# Radar_Digital.net
KiCad netlist of a schematic drawn in Altium Designer
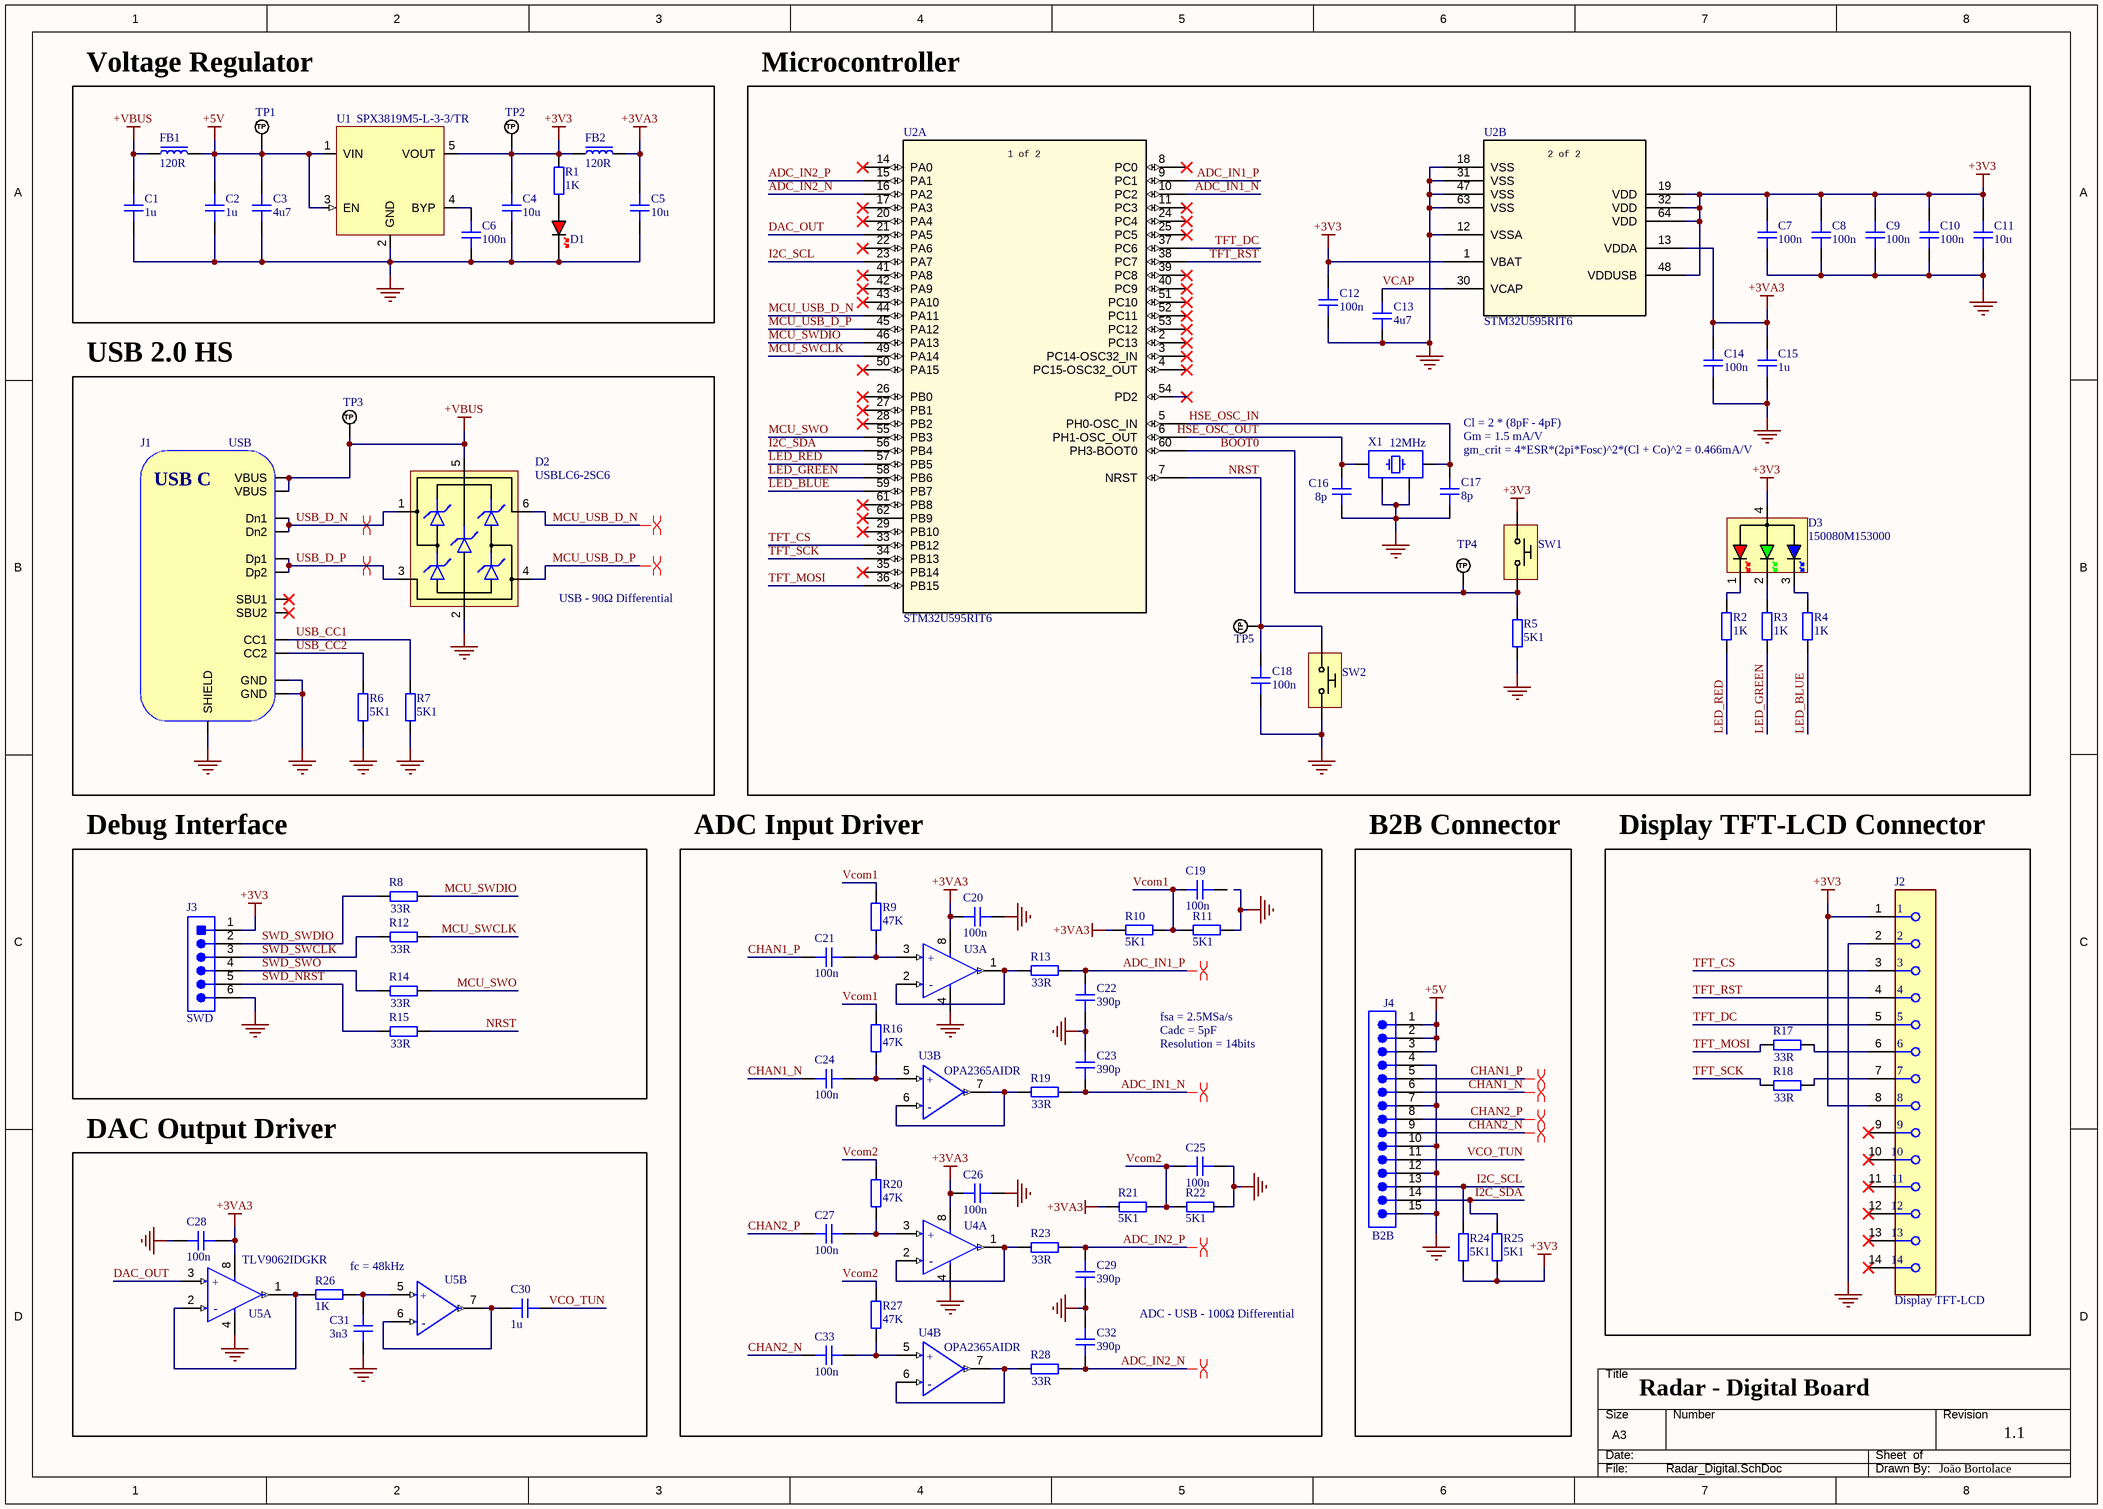
[diagram p0: Radar_Digital.SchDoc]

(export (version "E")
  (design (tool "Eeschema 10.0.6"))
  (components
    (comp (ref "C1")
      (value "1u")
      (footprint "CAP_0603")
      (description "1uF ±10% 25V Ceramic Capacitor X7R 0603")
      (fields
        (field (name "MANUFACTURER") "Samsung Electro-Mechanics")
        (field (name "MANUFACTURER PART NUMBER") "CL10B105KA8NNNC")
      )
      (libsource (lib "Schematic-Lib-PhilsLab") (part "CAP_0603"))
    )
    (comp (ref "C2")
      (value "1u")
      (footprint "CAP_0603")
      (description "1uF ±10% 25V Ceramic Capacitor X7R 0603")
      (fields
        (field (name "MANUFACTURER") "Samsung Electro-Mechanics")
        (field (name "MANUFACTURER PART NUMBER") "CL10B105KA8NNNC")
      )
      (libsource (lib "Schematic-Lib-PhilsLab") (part "CAP_0603"))
    )
    (comp (ref "C3")
      (value "4u7")
      (footprint "CAP_0603")
      (description "4.7uF ±10% 25V Ceramic Capacitor X5R 0603")
      (fields
        (field (name "MANUFACTURER") "Samsung Electro-Mechanics")
        (field (name "MANUFACTURER PART NUMBER") "CL10A475KA8NQNC")
      )
      (libsource (lib "Schematic-Lib-PhilsLab") (part "CAP_0603"))
    )
    (comp (ref "C4")
      (value "10u")
      (footprint "CAP_0805")
      (description "10uF ±10% 16V Ceramic Capacitor X7R 0805")
      (fields
        (field (name "MANUFACTURER") "Samsung Electro-Mechanics")
        (field (name "MANUFACTURER PART NUMBER") "CL21B106KOQNNNE")
      )
      (libsource (lib "Schematic-Lib-PhilsLab") (part "CAP_0805"))
    )
    (comp (ref "C5")
      (value "10u")
      (footprint "CAP_0805")
      (description "10uF ±10% 16V Ceramic Capacitor X7R 0805")
      (fields
        (field (name "MANUFACTURER") "Samsung Electro-Mechanics")
        (field (name "MANUFACTURER PART NUMBER") "CL21B106KOQNNNE")
      )
      (libsource (lib "Schematic-Lib-PhilsLab") (part "CAP_0805"))
    )
    (comp (ref "C6")
      (value "100n")
      (footprint "CAP_0603")
      (description "100nF ±10% 50V Ceramic Capacitor X7R 0603")
      (fields
        (field (name "MANUFACTURER") "Samsung Electro-Mechanics")
        (field (name "MANUFACTURER PART NUMBER") "CL10B104KB8NNNC")
      )
      (libsource (lib "Schematic-Lib-PhilsLab") (part "CAP_0603"))
    )
    (comp (ref "C7")
      (value "100n")
      (footprint "CAP_0603")
      (description "100nF ±10% 50V Ceramic Capacitor X7R 0603")
      (fields
        (field (name "MANUFACTURER") "Samsung Electro-Mechanics")
        (field (name "MANUFACTURER PART NUMBER") "CL10B104KB8NNNC")
      )
      (libsource (lib "Schematic-Lib-PhilsLab") (part "CAP_0603"))
    )
    (comp (ref "C8")
      (value "100n")
      (footprint "CAP_0603")
      (description "100nF ±10% 50V Ceramic Capacitor X7R 0603")
      (fields
        (field (name "MANUFACTURER") "Samsung Electro-Mechanics")
        (field (name "MANUFACTURER PART NUMBER") "CL10B104KB8NNNC")
      )
      (libsource (lib "Schematic-Lib-PhilsLab") (part "CAP_0603"))
    )
    (comp (ref "C9")
      (value "100n")
      (footprint "CAP_0603")
      (description "100nF ±10% 50V Ceramic Capacitor X7R 0603")
      (fields
        (field (name "MANUFACTURER") "Samsung Electro-Mechanics")
        (field (name "MANUFACTURER PART NUMBER") "CL10B104KB8NNNC")
      )
      (libsource (lib "Schematic-Lib-PhilsLab") (part "CAP_0603"))
    )
    (comp (ref "C10")
      (value "100n")
      (footprint "CAP_0603")
      (description "100nF ±10% 50V Ceramic Capacitor X7R 0603")
      (fields
        (field (name "MANUFACTURER") "Samsung Electro-Mechanics")
        (field (name "MANUFACTURER PART NUMBER") "CL10B104KB8NNNC")
      )
      (libsource (lib "Schematic-Lib-PhilsLab") (part "CAP_0603"))
    )
    (comp (ref "C11")
      (value "10u")
      (footprint "CAP_0805")
      (description "10uF ±10% 16V Ceramic Capacitor X7R 0805")
      (fields
        (field (name "MANUFACTURER") "Samsung Electro-Mechanics")
        (field (name "MANUFACTURER PART NUMBER") "CL21B106KOQNNNE")
      )
      (libsource (lib "Schematic-Lib-PhilsLab") (part "CAP_0805"))
    )
    (comp (ref "C12")
      (value "100n")
      (footprint "CAP_0603")
      (description "100nF ±10% 50V Ceramic Capacitor X7R 0603")
      (fields
        (field (name "MANUFACTURER") "Samsung Electro-Mechanics")
        (field (name "MANUFACTURER PART NUMBER") "CL10B104KB8NNNC")
      )
      (libsource (lib "Schematic-Lib-PhilsLab") (part "CAP_0603"))
    )
    (comp (ref "C13")
      (value "4u7")
      (footprint "CAP_0603")
      (description "4.7uF ±10% 25V Ceramic Capacitor X5R 0603")
      (fields
        (field (name "MANUFACTURER") "Samsung Electro-Mechanics")
        (field (name "MANUFACTURER PART NUMBER") "CL10A475KA8NQNC")
      )
      (libsource (lib "Schematic-Lib-PhilsLab") (part "CAP_0603"))
    )
    (comp (ref "C14")
      (value "100n")
      (footprint "CAP_0603")
      (description "100nF ±10% 50V Ceramic Capacitor X7R 0603")
      (fields
        (field (name "MANUFACTURER") "Samsung Electro-Mechanics")
        (field (name "MANUFACTURER PART NUMBER") "CL10B104KB8NNNC")
      )
      (libsource (lib "Schematic-Lib-PhilsLab") (part "CAP_0603"))
    )
    (comp (ref "C15")
      (value "1u")
      (footprint "CAP_0603")
      (description "1uF ±10% 25V Ceramic Capacitor X7R 0603")
      (fields
        (field (name "MANUFACTURER") "Samsung Electro-Mechanics")
        (field (name "MANUFACTURER PART NUMBER") "CL10B105KA8NNNC")
      )
      (libsource (lib "Schematic-Lib-PhilsLab") (part "CAP_0603"))
    )
    (comp (ref "C16")
      (value "8p")
      (footprint "CAP_0603")
      (description "8pF 50V Ceramic Capacitor NP0 0603")
      (fields
        (field (name "MANUFACTURER") "YAGEO")
        (field (name "MANUFACTURER PART NUMBER") "CC0603CRNPO9BN8R0")
      )
      (libsource (lib "Schematic-Lib-PhilsLab") (part "CAP_0603"))
    )
    (comp (ref "C17")
      (value "8p")
      (footprint "CAP_0603")
      (description "8pF 50V Ceramic Capacitor NP0 0603")
      (fields
        (field (name "MANUFACTURER") "YAGEO")
        (field (name "MANUFACTURER PART NUMBER") "CC0603CRNPO9BN8R0")
      )
      (libsource (lib "Schematic-Lib-PhilsLab") (part "CAP_0603"))
    )
    (comp (ref "C18")
      (value "100n")
      (footprint "CAP_0603")
      (description "100nF ±10% 50V Ceramic Capacitor X7R 0603")
      (fields
        (field (name "MANUFACTURER") "Samsung Electro-Mechanics")
        (field (name "MANUFACTURER PART NUMBER") "CL10B104KB8NNNC")
      )
      (libsource (lib "Schematic-Lib-PhilsLab") (part "CAP_0603"))
    )
    (comp (ref "C19")
      (value "100n")
      (footprint "CAP_0603")
      (description "100nF ±10% 50V Ceramic Capacitor X7R 0603")
      (fields
        (field (name "MANUFACTURER") "Samsung Electro-Mechanics")
        (field (name "MANUFACTURER PART NUMBER") "CL10B104KB8NNNC")
      )
      (libsource (lib "Schematic-Lib-PhilsLab") (part "CAP_0603"))
    )
    (comp (ref "C20")
      (value "100n")
      (footprint "CAP_0603")
      (description "100nF ±10% 50V Ceramic Capacitor X7R 0603")
      (fields
        (field (name "MANUFACTURER") "Samsung Electro-Mechanics")
        (field (name "MANUFACTURER PART NUMBER") "CL10B104KB8NNNC")
      )
      (libsource (lib "Schematic-Lib-PhilsLab") (part "CAP_0603"))
    )
    (comp (ref "C21")
      (value "100n")
      (footprint "CAP_0603")
      (description "100nF ±10% 50V Ceramic Capacitor X7R 0603")
      (fields
        (field (name "MANUFACTURER") "Samsung Electro-Mechanics")
        (field (name "MANUFACTURER PART NUMBER") "CL10B104KB8NNNC")
      )
      (libsource (lib "Schematic-Lib-PhilsLab") (part "CAP_0603"))
    )
    (comp (ref "C22")
      (value "390p")
      (footprint "CAP_0603")
      (description "390pF ±5% 50V Ceramic Capacitor C0G 0603")
      (fields
        (field (name "MANUFACTURER") "muRata")
        (field (name "MANUFACTURER PART NUMBER") "GRM1885C1H391JA01D")
      )
      (libsource (lib "Schematic-Lib-PhilsLab") (part "CAP_0603"))
    )
    (comp (ref "C23")
      (value "390p")
      (footprint "CAP_0603")
      (description "390pF ±5% 50V Ceramic Capacitor C0G 0603")
      (fields
        (field (name "MANUFACTURER") "muRata")
        (field (name "MANUFACTURER PART NUMBER") "GRM1885C1H391JA01D")
      )
      (libsource (lib "Schematic-Lib-PhilsLab") (part "CAP_0603"))
    )
    (comp (ref "C24")
      (value "100n")
      (footprint "CAP_0603")
      (description "100nF ±10% 50V Ceramic Capacitor X7R 0603")
      (fields
        (field (name "MANUFACTURER") "Samsung Electro-Mechanics")
        (field (name "MANUFACTURER PART NUMBER") "CL10B104KB8NNNC")
      )
      (libsource (lib "Schematic-Lib-PhilsLab") (part "CAP_0603"))
    )
    (comp (ref "C25")
      (value "100n")
      (footprint "CAP_0603")
      (description "100nF ±10% 50V Ceramic Capacitor X7R 0603")
      (fields
        (field (name "MANUFACTURER") "Samsung Electro-Mechanics")
        (field (name "MANUFACTURER PART NUMBER") "CL10B104KB8NNNC")
      )
      (libsource (lib "Schematic-Lib-PhilsLab") (part "CAP_0603"))
    )
    (comp (ref "C26")
      (value "100n")
      (footprint "CAP_0603")
      (description "100nF ±10% 50V Ceramic Capacitor X7R 0603")
      (fields
        (field (name "MANUFACTURER") "Samsung Electro-Mechanics")
        (field (name "MANUFACTURER PART NUMBER") "CL10B104KB8NNNC")
      )
      (libsource (lib "Schematic-Lib-PhilsLab") (part "CAP_0603"))
    )
    (comp (ref "C27")
      (value "100n")
      (footprint "CAP_0603")
      (description "100nF ±10% 50V Ceramic Capacitor X7R 0603")
      (fields
        (field (name "MANUFACTURER") "Samsung Electro-Mechanics")
        (field (name "MANUFACTURER PART NUMBER") "CL10B104KB8NNNC")
      )
      (libsource (lib "Schematic-Lib-PhilsLab") (part "CAP_0603"))
    )
    (comp (ref "C28")
      (value "100n")
      (footprint "CAP_0603")
      (description "100nF ±10% 50V Ceramic Capacitor X7R 0603")
      (fields
        (field (name "MANUFACTURER") "Samsung Electro-Mechanics")
        (field (name "MANUFACTURER PART NUMBER") "CL10B104KB8NNNC")
      )
      (libsource (lib "Schematic-Lib-PhilsLab") (part "CAP_0603"))
    )
    (comp (ref "C29")
      (value "390p")
      (footprint "CAP_0603")
      (description "390pF ±5% 50V Ceramic Capacitor C0G 0603")
      (fields
        (field (name "MANUFACTURER") "muRata")
        (field (name "MANUFACTURER PART NUMBER") "GRM1885C1H391JA01D")
      )
      (libsource (lib "Schematic-Lib-PhilsLab") (part "CAP_0603"))
    )
    (comp (ref "C30")
      (value "1u")
      (footprint "CAP_0603")
      (description "1uF ±10% 25V Ceramic Capacitor X7R 0603")
      (fields
        (field (name "MANUFACTURER") "Samsung Electro-Mechanics")
        (field (name "MANUFACTURER PART NUMBER") "CL10B105KA8NNNC")
      )
      (libsource (lib "Schematic-Lib-PhilsLab") (part "CAP_0603"))
    )
    (comp (ref "C31")
      (value "3n3")
      (footprint "CAP_0603")
      (description "3.3nF ±10% 50V Ceramic Capacitor X7R 0603")
      (fields
        (field (name "MANUFACTURER") "Samsung Electro-Mechanics")
        (field (name "MANUFACTURER PART NUMBER") "CL10B332KB8NNNC")
      )
      (libsource (lib "Schematic-Lib-PhilsLab") (part "CAP_0603"))
    )
    (comp (ref "C32")
      (value "390p")
      (footprint "CAP_0603")
      (description "390pF ±5% 50V Ceramic Capacitor C0G 0603")
      (fields
        (field (name "MANUFACTURER") "muRata")
        (field (name "MANUFACTURER PART NUMBER") "GRM1885C1H391JA01D")
      )
      (libsource (lib "Schematic-Lib-PhilsLab") (part "CAP_0603"))
    )
    (comp (ref "C33")
      (value "100n")
      (footprint "CAP_0603")
      (description "100nF ±10% 50V Ceramic Capacitor X7R 0603")
      (fields
        (field (name "MANUFACTURER") "Samsung Electro-Mechanics")
        (field (name "MANUFACTURER PART NUMBER") "CL10B104KB8NNNC")
      )
      (libsource (lib "Schematic-Lib-PhilsLab") (part "CAP_0603"))
    )
    (comp (ref "D1")
      (value "ON")
      (footprint "LED_0603_RED")
      (description "Red 625nm LED Indication - Discrete 2.3V 0603")
      (fields
        (field (name "MANUFACTURER") "XINGLIGHT")
        (field (name "MANUFACTURER PART NUMBER") "XL-1608SURC-06")
      )
      (libsource (lib "Schematic-Lib-PhilsLab") (part "LED_0603_RED"))
    )
    (comp (ref "D2")
      (value "USBLC6-2SC6")
      (footprint "SOT-23-6")
      (description "Low-Capacitance ESD Protection USB")
      (fields (field (name "MANUFACTURER") "STMicroelectronics"))
      (libsource (lib "Schematic-Lib-PhilsLab") (part "USBLC6-2SC6"))
    )
    (comp (ref "D3")
      (value "150080M153000")
      (footprint "150080M153000")
      (description "Water Clear SMD-4P,2x1.2mm LED Indication - Discrete RoHS")
      (fields
        (field (name "MANUFACTURER") "XINGLIGHT")
        (field (name "MANUFACTURER PART NUMBER") "XL-2012RGBC")
      )
      (libsource (lib "Schematic-Lib-PhilsLab") (part "150080M153000"))
    )
    (comp (ref "FB1")
      (value "120R")
      (footprint "FB_0603")
      (description "120Ω@100MHz 1 Line Ferrite Bead 0603 2A 50mΩ")
      (fields
        (field (name "MANUFACTURER") "muRata")
        (field (name "MANUFACTURER PART NUMBER") "BLM18PG121SN1D")
      )
      (libsource (lib "Schematic-Lib-PhilsLab") (part "FB_0603"))
    )
    (comp (ref "FB2")
      (value "120R")
      (footprint "FB_0603")
      (description "120Ω@100MHz 1 Line Ferrite Bead 0603 2A 50mΩ")
      (fields
        (field (name "MANUFACTURER") "muRata")
        (field (name "MANUFACTURER PART NUMBER") "BLM18PG121SN1D")
      )
      (libsource (lib "Schematic-Lib-PhilsLab") (part "FB_0603"))
    )
    (comp (ref "J1")
      (value "USB")
      (footprint "USB4105-GF-A-060")
      (description "USB-C (USB TYPE-C) Receptacle Connector 16 Position Surface Mount, Right Angle")
      (fields
        (field (name "MANUFACTURER") "SHOU HAN")
        (field (name "MANUFACTURER PART NUMBER") "TYPE-C 16PIN 2MD(073)")
      )
      (libsource (lib "Schematic-Lib-PhilsLab") (part "USB4105-GF-A-060"))
    )
    (comp (ref "J2")
      (value "Display TFT-LCD")
      (footprint "FP-SSQ-114-01-G-S-MFG")
      (description "CONN RCPT 14POS 0.1 GOLD PCB")
      (libsource (lib "Altium Content Vault") (part "d5edc8e6a7a3a19823a41f215fe8be2"))
    )
    (comp (ref "J3")
      (value "SWD")
      (footprint "SMTC-TSW-106-07-S-S_V")
      (fields (field (name "MANUFACTURER") "Samtec"))
      (libsource (lib "Altium Content Vault") (part "CN-1P-M-R6"))
    )
    (comp (ref "J4")
      (value "B2B")
      (footprint "61301511121")
      (description "Conn Unshrouded Header HDR 15 POS 2.54mm Solder ST Top Entry Thru-Hole Bag")
      (libsource (lib "Altium Content Vault") (part "Header_Male_1R_15P"))
    )
    (comp (ref "R1")
      (value "1K")
      (footprint "RES_0603")
      (description "100mW 1kΩ 75V Thick Film Resistor ±100ppm/℃ ±1% 0603 Chip Resistor - Surface Mount RoHS")
      (fields
        (field (name "MANUFACTURER") "YAGEO")
        (field (name "MANUFACTURER PART NUMBER") "RC0603FR-071KL")
      )
      (libsource (lib "Schematic-Lib-PhilsLab") (part "RES_0603"))
    )
    (comp (ref "R2")
      (value "1K")
      (footprint "RES_0603")
      (description "100mW 1kΩ 75V Thick Film Resistor ±100ppm/℃ ±1% 0603 Chip Resistor - Surface Mount RoHS")
      (fields
        (field (name "MANUFACTURER") "YAGEO")
        (field (name "MANUFACTURER PART NUMBER") "RC0603FR-071KL")
      )
      (libsource (lib "Schematic-Lib-PhilsLab") (part "RES_0603"))
    )
    (comp (ref "R3")
      (value "1K")
      (footprint "RES_0603")
      (description "100mW 1kΩ 75V Thick Film Resistor ±100ppm/℃ ±1% 0603 Chip Resistor - Surface Mount RoHS")
      (fields
        (field (name "MANUFACTURER") "YAGEO")
        (field (name "MANUFACTURER PART NUMBER") "RC0603FR-071KL")
      )
      (libsource (lib "Schematic-Lib-PhilsLab") (part "RES_0603"))
    )
    (comp (ref "R4")
      (value "1K")
      (footprint "RES_0603")
      (description "100mW 1kΩ 75V Thick Film Resistor ±100ppm/℃ ±1% 0603 Chip Resistor - Surface Mount RoHS")
      (fields
        (field (name "MANUFACTURER") "YAGEO")
        (field (name "MANUFACTURER PART NUMBER") "RC0603FR-071KL")
      )
      (libsource (lib "Schematic-Lib-PhilsLab") (part "RES_0603"))
    )
    (comp (ref "R5")
      (value "5K1")
      (footprint "RES_0603")
      (description "100mW 5.1kΩ 75V Thick Film Resistor ±100ppm/℃ ±1% 0603 Chip Resistor - Surface Mount RoHS")
      (fields
        (field (name "MANUFACTURER") "YAGEO")
        (field (name "MANUFACTURER PART NUMBER") "RC0603FR-075K1L")
      )
      (libsource (lib "Schematic-Lib-PhilsLab") (part "RES_0603"))
    )
    (comp (ref "R6")
      (value "5K1")
      (footprint "RES_0603")
      (description "100mW 5.1kΩ 75V Thick Film Resistor ±100ppm/℃ ±1% 0603 Chip Resistor - Surface Mount RoHS")
      (fields
        (field (name "MANUFACTURER") "YAGEO")
        (field (name "MANUFACTURER PART NUMBER") "RC0603FR-075K1L")
      )
      (libsource (lib "Schematic-Lib-PhilsLab") (part "RES_0603"))
    )
    (comp (ref "R7")
      (value "5K1")
      (footprint "RES_0603")
      (description "100mW 5.1kΩ 75V Thick Film Resistor ±100ppm/℃ ±1% 0603 Chip Resistor - Surface Mount RoHS")
      (fields
        (field (name "MANUFACTURER") "YAGEO")
        (field (name "MANUFACTURER PART NUMBER") "RC0603FR-075K1L")
      )
      (libsource (lib "Schematic-Lib-PhilsLab") (part "RES_0603"))
    )
    (comp (ref "R8")
      (value "33R")
      (footprint "RES_0603")
      (description "100mW 33Ω 75V Thick Film Resistor ±100ppm/℃ ±1% 0603 Chip Resistor - Surface Mount RoHS")
      (fields
        (field (name "MANUFACTURER") "YAGEO")
        (field (name "MANUFACTURER PART NUMBER") "RC0603FR-0733RL")
      )
      (libsource (lib "Schematic-Lib-PhilsLab") (part "RES_0603"))
    )
    (comp (ref "R9")
      (value "47K")
      (footprint "RES_0603")
      (description "100mW 47kΩ 75V Thick Film Resistor ±100ppm/℃ ±1% 0603 Chip Resistor - Surface Mount RoHS")
      (fields
        (field (name "MANUFACTURER") "YAGEO")
        (field (name "MANUFACTURER PART NUMBER") "RC0603FR-0747KL")
      )
      (libsource (lib "Schematic-Lib-PhilsLab") (part "RES_0603"))
    )
    (comp (ref "R10")
      (value "5K1")
      (footprint "RES_0603")
      (description "100mW 5.1kΩ 75V Thick Film Resistor ±100ppm/℃ ±1% 0603 Chip Resistor - Surface Mount RoHS")
      (fields
        (field (name "MANUFACTURER") "YAGEO")
        (field (name "MANUFACTURER PART NUMBER") "RC0603FR-075K1L")
      )
      (libsource (lib "Schematic-Lib-PhilsLab") (part "RES_0603"))
    )
    (comp (ref "R11")
      (value "5K1")
      (footprint "RES_0603")
      (description "100mW 5.1kΩ 75V Thick Film Resistor ±100ppm/℃ ±1% 0603 Chip Resistor - Surface Mount RoHS")
      (fields
        (field (name "MANUFACTURER") "YAGEO")
        (field (name "MANUFACTURER PART NUMBER") "RC0603FR-075K1L")
      )
      (libsource (lib "Schematic-Lib-PhilsLab") (part "RES_0603"))
    )
    (comp (ref "R12")
      (value "33R")
      (footprint "RES_0603")
      (description "100mW 33Ω 75V Thick Film Resistor ±100ppm/℃ ±1% 0603 Chip Resistor - Surface Mount RoHS")
      (fields
        (field (name "MANUFACTURER") "YAGEO")
        (field (name "MANUFACTURER PART NUMBER") "RC0603FR-0733RL")
      )
      (libsource (lib "Schematic-Lib-PhilsLab") (part "RES_0603"))
    )
    (comp (ref "R13")
      (value "33R")
      (footprint "RES_0603")
      (description "100mW 33Ω 75V Thick Film Resistor ±100ppm/℃ ±1% 0603 Chip Resistor - Surface Mount RoHS")
      (fields
        (field (name "MANUFACTURER") "YAGEO")
        (field (name "MANUFACTURER PART NUMBER") "RC0603FR-0733RL")
      )
      (libsource (lib "Schematic-Lib-PhilsLab") (part "RES_0603"))
    )
    (comp (ref "R14")
      (value "33R")
      (footprint "RES_0603")
      (description "100mW 33Ω 75V Thick Film Resistor ±100ppm/℃ ±1% 0603 Chip Resistor - Surface Mount RoHS")
      (fields
        (field (name "MANUFACTURER") "YAGEO")
        (field (name "MANUFACTURER PART NUMBER") "RC0603FR-0733RL")
      )
      (libsource (lib "Schematic-Lib-PhilsLab") (part "RES_0603"))
    )
    (comp (ref "R15")
      (value "33R")
      (footprint "RES_0603")
      (description "100mW 33Ω 75V Thick Film Resistor ±100ppm/℃ ±1% 0603 Chip Resistor - Surface Mount RoHS")
      (fields
        (field (name "MANUFACTURER") "YAGEO")
        (field (name "MANUFACTURER PART NUMBER") "RC0603FR-0733RL")
      )
      (libsource (lib "Schematic-Lib-PhilsLab") (part "RES_0603"))
    )
    (comp (ref "R16")
      (value "47K")
      (footprint "RES_0603")
      (description "100mW 47kΩ 75V Thick Film Resistor ±100ppm/℃ ±1% 0603 Chip Resistor - Surface Mount RoHS")
      (fields
        (field (name "MANUFACTURER") "YAGEO")
        (field (name "MANUFACTURER PART NUMBER") "RC0603FR-0747KL")
      )
      (libsource (lib "Schematic-Lib-PhilsLab") (part "RES_0603"))
    )
    (comp (ref "R17")
      (value "33R")
      (footprint "RES_0603")
      (description "100mW 33Ω 75V Thick Film Resistor ±100ppm/℃ ±1% 0603 Chip Resistor - Surface Mount RoHS")
      (fields
        (field (name "MANUFACTURER") "YAGEO")
        (field (name "MANUFACTURER PART NUMBER") "RC0603FR-0733RL")
      )
      (libsource (lib "Schematic-Lib-PhilsLab") (part "RES_0603"))
    )
    (comp (ref "R18")
      (value "33R")
      (footprint "RES_0603")
      (description "100mW 33Ω 75V Thick Film Resistor ±100ppm/℃ ±1% 0603 Chip Resistor - Surface Mount RoHS")
      (fields
        (field (name "MANUFACTURER") "YAGEO")
        (field (name "MANUFACTURER PART NUMBER") "RC0603FR-0733RL")
      )
      (libsource (lib "Schematic-Lib-PhilsLab") (part "RES_0603"))
    )
    (comp (ref "R19")
      (value "33R")
      (footprint "RES_0603")
      (description "100mW 33Ω 75V Thick Film Resistor ±100ppm/℃ ±1% 0603 Chip Resistor - Surface Mount RoHS")
      (fields
        (field (name "MANUFACTURER") "YAGEO")
        (field (name "MANUFACTURER PART NUMBER") "RC0603FR-0733RL")
      )
      (libsource (lib "Schematic-Lib-PhilsLab") (part "RES_0603"))
    )
    (comp (ref "R20")
      (value "47K")
      (footprint "RES_0603")
      (description "100mW 47kΩ 75V Thick Film Resistor ±100ppm/℃ ±1% 0603 Chip Resistor - Surface Mount RoHS")
      (fields
        (field (name "MANUFACTURER") "YAGEO")
        (field (name "MANUFACTURER PART NUMBER") "RC0603FR-0747KL")
      )
      (libsource (lib "Schematic-Lib-PhilsLab") (part "RES_0603"))
    )
    (comp (ref "R21")
      (value "5K1")
      (footprint "RES_0603")
      (description "100mW 5.1kΩ 75V Thick Film Resistor ±100ppm/℃ ±1% 0603 Chip Resistor - Surface Mount RoHS")
      (fields
        (field (name "MANUFACTURER") "YAGEO")
        (field (name "MANUFACTURER PART NUMBER") "RC0603FR-075K1L")
      )
      (libsource (lib "Schematic-Lib-PhilsLab") (part "RES_0603"))
    )
    (comp (ref "R22")
      (value "5K1")
      (footprint "RES_0603")
      (description "100mW 5.1kΩ 75V Thick Film Resistor ±100ppm/℃ ±1% 0603 Chip Resistor - Surface Mount RoHS")
      (fields
        (field (name "MANUFACTURER") "YAGEO")
        (field (name "MANUFACTURER PART NUMBER") "RC0603FR-075K1L")
      )
      (libsource (lib "Schematic-Lib-PhilsLab") (part "RES_0603"))
    )
    (comp (ref "R23")
      (value "33R")
      (footprint "RES_0603")
      (description "100mW 33Ω 75V Thick Film Resistor ±100ppm/℃ ±1% 0603 Chip Resistor - Surface Mount RoHS")
      (fields
        (field (name "MANUFACTURER") "YAGEO")
        (field (name "MANUFACTURER PART NUMBER") "RC0603FR-0733RL")
      )
      (libsource (lib "Schematic-Lib-PhilsLab") (part "RES_0603"))
    )
    (comp (ref "R24")
      (value "5K1")
      (footprint "RES_0603")
      (description "100mW 5.1kΩ 75V Thick Film Resistor ±100ppm/℃ ±1% 0603 Chip Resistor - Surface Mount RoHS")
      (fields
        (field (name "MANUFACTURER") "YAGEO")
        (field (name "MANUFACTURER PART NUMBER") "RC0603FR-075K1L")
      )
      (libsource (lib "Schematic-Lib-PhilsLab") (part "RES_0603"))
    )
    (comp (ref "R25")
      (value "5K1")
      (footprint "RES_0603")
      (description "100mW 5.1kΩ 75V Thick Film Resistor ±100ppm/℃ ±1% 0603 Chip Resistor - Surface Mount RoHS")
      (fields
        (field (name "MANUFACTURER") "YAGEO")
        (field (name "MANUFACTURER PART NUMBER") "RC0603FR-075K1L")
      )
      (libsource (lib "Schematic-Lib-PhilsLab") (part "RES_0603"))
    )
    (comp (ref "R26")
      (value "1K")
      (footprint "RES_0603")
      (description "100mW 1kΩ 75V Thick Film Resistor ±100ppm/℃ ±1% 0603 Chip Resistor - Surface Mount RoHS")
      (fields
        (field (name "MANUFACTURER") "YAGEO")
        (field (name "MANUFACTURER PART NUMBER") "RC0603FR-071KL")
      )
      (libsource (lib "Schematic-Lib-PhilsLab") (part "RES_0603"))
    )
    (comp (ref "R27")
      (value "47K")
      (footprint "RES_0603")
      (description "100mW 47kΩ 75V Thick Film Resistor ±100ppm/℃ ±1% 0603 Chip Resistor - Surface Mount RoHS")
      (fields
        (field (name "MANUFACTURER") "YAGEO")
        (field (name "MANUFACTURER PART NUMBER") "RC0603FR-0747KL")
      )
      (libsource (lib "Schematic-Lib-PhilsLab") (part "RES_0603"))
    )
    (comp (ref "R28")
      (value "33R")
      (footprint "RES_0603")
      (description "100mW 33Ω 75V Thick Film Resistor ±100ppm/℃ ±1% 0603 Chip Resistor - Surface Mount RoHS")
      (fields
        (field (name "MANUFACTURER") "YAGEO")
        (field (name "MANUFACTURER PART NUMBER") "RC0603FR-0733RL")
      )
      (libsource (lib "Schematic-Lib-PhilsLab") (part "RES_0603"))
    )
    (comp (ref "SW1")
      (value "BOOT")
      (footprint "PTS815")
      (description "Tactile Switch SPST 400gf 2.5mm 4.2mm x 3.2mm Surface Mount")
      (fields
        (field (name "MANUFACTURER") "G-Switch")
        (field (name "MANUFACTURER PART NUMBER") "GT-TC048D-H025-L1")
      )
      (libsource (lib "Schematic-Lib-PhilsLab") (part "PTS815-SJM-250-SMTR-LFS"))
    )
    (comp (ref "SW2")
      (value "RST")
      (footprint "PTS815")
      (description "Tactile Switch SPST 400gf 2.5mm 4.2mm x 3.2mm Surface Mount")
      (fields
        (field (name "MANUFACTURER") "G-Switch")
        (field (name "MANUFACTURER PART NUMBER") "GT-TC048D-H025-L1")
      )
      (libsource (lib "Schematic-Lib-PhilsLab") (part "PTS815-SJM-250-SMTR-LFS"))
    )
    (comp (ref "TP1")
      (value "TP_NOBOM")
      (footprint "PAD_RND_1MM")
      (description "Test Point Round 1mm (NO BOM)")
      (libsource (lib "Schematic-Lib-PhilsLab") (part "TEST_POINT_RND_1MM"))
    )
    (comp (ref "TP2")
      (value "TP_NOBOM")
      (footprint "PAD_RND_1MM")
      (description "Test Point Round 1mm (NO BOM)")
      (libsource (lib "Schematic-Lib-PhilsLab") (part "TEST_POINT_RND_1MM"))
    )
    (comp (ref "TP3")
      (value "TP_NOBOM")
      (footprint "PAD_RND_1MM")
      (description "Test Point Round 1mm (NO BOM)")
      (libsource (lib "Schematic-Lib-PhilsLab") (part "TEST_POINT_RND_1MM"))
    )
    (comp (ref "TP4")
      (value "TP_NOBOM")
      (footprint "PAD_RND_1MM")
      (description "Test Point Round 1mm (NO BOM)")
      (libsource (lib "Schematic-Lib-PhilsLab") (part "TEST_POINT_RND_1MM"))
    )
    (comp (ref "TP5")
      (value "TP_NOBOM")
      (footprint "PAD_RND_1MM")
      (description "Test Point Round 1mm (NO BOM)")
      (libsource (lib "Schematic-Lib-PhilsLab") (part "TEST_POINT_RND_1MM"))
    )
    (comp (ref "U1")
      (value "SPX3819M5-L-3-3/TR")
      (footprint "SOT-23-5")
      (description "500mA +3.3V Low-Noise LDO Voltage Regulator")
      (fields (field (name "MANUFACTURER") "MaxLinear"))
      (libsource (lib "Schematic-Lib-PhilsLab") (part "SPX3819M5-L-3-3/TR"))
    )
    (comp (ref "U2")
      (value "STM32U595RIT6")
      (footprint "LQFP64-10x10mm_STM")
      (description "Ultra-low-power with FPU Arm Cortex-M33 MCU with TrustZone, 160 MHz with 2 Mbytes of Flash memory")
      (fields
        (field (name "MANUFACTURER") "STMicroelectronics")
        (field (name "COPYRIGHT") "Copyright (C) 2025 Ultra Librarian. All rights reserved.")
      )
      (libsource (lib "STM32U595RIT6") (part "STM32U595RIT6"))
    )
    (comp (ref "U3")
      (value "OPA2365AIDR")
      (footprint "FP-D0008A-MFG")
      (description "IC OPAMP GP 2 CIRCUIT 8SOIC")
      (fields (field (name "MANUFACTURER") "TI"))
      (libsource (lib "Altium Content Vault") (part "9ca2bc73342ca7483af30a08cc44e28"))
    )
    (comp (ref "U4")
      (value "OPA2365AIDR")
      (footprint "FP-D0008A-MFG")
      (description "IC OPAMP GP 2 CIRCUIT 8SOIC")
      (fields (field (name "MANUFACTURER") "TI"))
      (libsource (lib "Altium Content Vault") (part "9ca2bc73342ca7483af30a08cc44e28"))
    )
    (comp (ref "U5")
      (value "TLV9062IDGKR")
      (footprint "FP-DGK0008A-IPC_A")
      (description "IC CMOS 2 CIRCUIT 8VSSOP")
      (fields (field (name "TOLERANCE") "0.1%") (field (name "MANUFACTURER") "TI"))
      (libsource (lib "Altium Content Vault") (part "d5b36c1049528187b1d2197d5d58d7e"))
    )
    (comp (ref "X1")
      (value "12MHz")
      (footprint "XTAL_3225")
      (description "Crystal 12MHz ±15ppm 8pF 120Ω SMD3225-4P")
      (fields (field (name "MANUFACTURER") "DIODES") (field (name "MANUFACTURER PART NUMBER") "FL1200138"))
      (libsource (lib "Schematic-Lib-PhilsLab") (part "TSX-3225_24.0000MF15X-AC"))
    )
  )
  (nets
    (net (code "1") (name "+3V3") (class "Default")
      (node (ref "C10") (pin "2") (pinfunction "2_2") (pintype "passive"))
      (node (ref "C11") (pin "2") (pinfunction "2_2") (pintype "passive"))
      (node (ref "C12") (pin "2") (pinfunction "2_2") (pintype "passive"))
      (node (ref "C4") (pin "2") (pinfunction "2_2") (pintype "passive"))
      (node (ref "C7") (pin "2") (pinfunction "2_2") (pintype "passive"))
      (node (ref "C8") (pin "2") (pinfunction "2_2") (pintype "passive"))
      (node (ref "C9") (pin "2") (pinfunction "2_2") (pintype "passive"))
      (node (ref "D3") (pin "4") (pinfunction "AC_4") (pintype "passive"))
      (node (ref "FB2") (pin "1") (pinfunction "1_1") (pintype "passive"))
      (node (ref "J2") (pin "1") (pinfunction "1_1") (pintype "passive"))
      (node (ref "J2") (pin "8") (pinfunction "8_8") (pintype "passive"))
      (node (ref "J3") (pin "1") (pinfunction "1_1") (pintype "passive"))
      (node (ref "R1") (pin "1") (pinfunction "1_1") (pintype "passive"))
      (node (ref "R24") (pin "1") (pinfunction "1_1") (pintype "passive"))
      (node (ref "R25") (pin "1") (pinfunction "1_1") (pintype "passive"))
      (node (ref "SW1") (pin "1") (pinfunction "1_1") (pintype "passive"))
      (node (ref "TP2") (pin "1") (pinfunction "TP_1") (pintype "passive"))
      (node (ref "U1") (pin "5") (pinfunction "VOUT_5") (pintype "power_in"))
      (node (ref "U2") (pin "1") (pinfunction "VBAT_1") (pintype "power_in"))
      (node (ref "U2") (pin "19") (pinfunction "VDD_19") (pintype "power_in"))
      (node (ref "U2") (pin "32") (pinfunction "VDD_32") (pintype "power_in"))
      (node (ref "U2") (pin "48") (pinfunction "VDDUSB_48") (pintype "power_in"))
      (node (ref "U2") (pin "64") (pinfunction "VDD_64") (pintype "power_in"))
    )
    (net (code "2") (name "+3VA3") (class "Default")
      (node (ref "C14") (pin "2") (pinfunction "2_2") (pintype "passive"))
      (node (ref "C15") (pin "2") (pinfunction "2_2") (pintype "passive"))
      (node (ref "C20") (pin "2") (pinfunction "2_2") (pintype "passive"))
      (node (ref "C26") (pin "2") (pinfunction "2_2") (pintype "passive"))
      (node (ref "C28") (pin "2") (pinfunction "2_2") (pintype "passive"))
      (node (ref "C5") (pin "2") (pinfunction "2_2") (pintype "passive"))
      (node (ref "FB2") (pin "2") (pinfunction "2_2") (pintype "passive"))
      (node (ref "R10") (pin "2") (pinfunction "2_2") (pintype "passive"))
      (node (ref "R21") (pin "2") (pinfunction "2_2") (pintype "passive"))
      (node (ref "U2") (pin "13") (pinfunction "VDDA_13") (pintype "power_in"))
      (node (ref "U3") (pin "8") (pinfunction "V+_8") (pintype "power_in"))
      (node (ref "U4") (pin "8") (pinfunction "V+_8") (pintype "power_in"))
      (node (ref "U5") (pin "8") (pinfunction "V+_8") (pintype "power_in"))
    )
    (net (code "3") (name "+5V") (class "Default")
      (node (ref "C2") (pin "2") (pinfunction "2_2") (pintype "passive"))
      (node (ref "C3") (pin "2") (pinfunction "2_2") (pintype "passive"))
      (node (ref "FB1") (pin "2") (pinfunction "2_2") (pintype "passive"))
      (node (ref "J4") (pin "1") (pinfunction "1_1") (pintype "passive"))
      (node (ref "J4") (pin "2") (pinfunction "2_2") (pintype "passive"))
      (node (ref "J4") (pin "3") (pinfunction "3_3") (pintype "passive"))
      (node (ref "TP1") (pin "1") (pinfunction "TP_1") (pintype "passive"))
      (node (ref "U1") (pin "1") (pinfunction "VIN_1") (pintype "power_in"))
      (node (ref "U1") (pin "3") (pinfunction "EN_3") (pintype "input"))
    )
    (net (code "4") (name "+VBUS") (class "Default")
      (node (ref "C1") (pin "2") (pinfunction "2_2") (pintype "passive"))
      (node (ref "D2") (pin "5") (pinfunction "VBUS_5") (pintype "power_in"))
      (node (ref "FB1") (pin "1") (pinfunction "1_1") (pintype "passive"))
      (node (ref "J1") (pin "A4B9") (pinfunction "VBUS_A4B9") (pintype "passive"))
      (node (ref "J1") (pin "B4A9") (pinfunction "VBUS_B4A9") (pintype "passive"))
      (node (ref "TP3") (pin "1") (pinfunction "TP_1") (pintype "passive"))
    )
    (net (code "5") (name "/ADC_IN1_N") (class "Default")
      (node (ref "C23") (pin "1") (pinfunction "1_1") (pintype "passive"))
      (node (ref "R19") (pin "2") (pinfunction "2_2") (pintype "passive"))
      (node (ref "U2") (pin "10") (pinfunction "PC2_10") (pintype "bidirectional"))
    )
    (net (code "6") (name "/ADC_IN1_P") (class "Default")
      (node (ref "C22") (pin "2") (pinfunction "2_2") (pintype "passive"))
      (node (ref "R13") (pin "2") (pinfunction "2_2") (pintype "passive"))
      (node (ref "U2") (pin "9") (pinfunction "PC1_9") (pintype "bidirectional"))
    )
    (net (code "7") (name "/ADC_IN2_N") (class "Default")
      (node (ref "C32") (pin "1") (pinfunction "1_1") (pintype "passive"))
      (node (ref "R28") (pin "2") (pinfunction "2_2") (pintype "passive"))
      (node (ref "U2") (pin "16") (pinfunction "PA2_16") (pintype "bidirectional"))
    )
    (net (code "8") (name "/ADC_IN2_P") (class "Default")
      (node (ref "C29") (pin "2") (pinfunction "2_2") (pintype "passive"))
      (node (ref "R23") (pin "2") (pinfunction "2_2") (pintype "passive"))
      (node (ref "U2") (pin "15") (pinfunction "PA1_15") (pintype "bidirectional"))
    )
    (net (code "9") (name "/BOOT0") (class "Default")
      (node (ref "R5") (pin "2") (pinfunction "2_2") (pintype "passive"))
      (node (ref "SW1") (pin "2") (pinfunction "2_2") (pintype "passive"))
      (node (ref "TP4") (pin "1") (pinfunction "TP_1") (pintype "passive"))
      (node (ref "U2") (pin "60") (pinfunction "PH3-BOOT0_60") (pintype "bidirectional"))
    )
    (net (code "10") (name "/CHAN1_N") (class "Default")
      (node (ref "C24") (pin "2") (pinfunction "2_2") (pintype "passive"))
      (node (ref "J4") (pin "6") (pinfunction "6_6") (pintype "passive"))
    )
    (net (code "11") (name "/CHAN1_P") (class "Default")
      (node (ref "C21") (pin "2") (pinfunction "2_2") (pintype "passive"))
      (node (ref "J4") (pin "5") (pinfunction "5_5") (pintype "passive"))
    )
    (net (code "12") (name "/CHAN2_N") (class "Default")
      (node (ref "C33") (pin "2") (pinfunction "2_2") (pintype "passive"))
      (node (ref "J4") (pin "9") (pinfunction "9_9") (pintype "passive"))
    )
    (net (code "13") (name "/CHAN2_P") (class "Default")
      (node (ref "C27") (pin "2") (pinfunction "2_2") (pintype "passive"))
      (node (ref "J4") (pin "8") (pinfunction "8_8") (pintype "passive"))
    )
    (net (code "14") (name "/DAC_OUT") (class "Default")
      (node (ref "U2") (pin "21") (pinfunction "PA5_21") (pintype "bidirectional"))
      (node (ref "U5") (pin "3") (pinfunction "IN1+_3") (pintype "tri_state"))
    )
    (net (code "15") (name "/HSE_OSC_IN") (class "Default")
      (node (ref "C17") (pin "2") (pinfunction "2_2") (pintype "passive"))
      (node (ref "U2") (pin "5") (pinfunction "PH0-OSC_IN_5") (pintype "bidirectional"))
      (node (ref "X1") (pin "3") (pinfunction "3_3") (pintype "passive"))
    )
    (net (code "16") (name "/HSE_OSC_OUT") (class "Default")
      (node (ref "C16") (pin "2") (pinfunction "2_2") (pintype "passive"))
      (node (ref "U2") (pin "6") (pinfunction "PH1-OSC_OUT_6") (pintype "bidirectional"))
      (node (ref "X1") (pin "1") (pinfunction "1_1") (pintype "passive"))
    )
    (net (code "17") (name "/I2C_SCL") (class "Default")
      (node (ref "J4") (pin "13") (pinfunction "13_13") (pintype "passive"))
      (node (ref "R24") (pin "2") (pinfunction "2_2") (pintype "passive"))
      (node (ref "U2") (pin "23") (pinfunction "PA7_23") (pintype "bidirectional"))
    )
    (net (code "18") (name "/I2C_SDA") (class "Default")
      (node (ref "J4") (pin "14") (pinfunction "14_14") (pintype "passive"))
      (node (ref "R25") (pin "2") (pinfunction "2_2") (pintype "passive"))
      (node (ref "U2") (pin "56") (pinfunction "PB4_56") (pintype "bidirectional"))
    )
    (net (code "19") (name "/LED_BLUE") (class "Default")
      (node (ref "R4") (pin "2") (pinfunction "2_2") (pintype "passive"))
      (node (ref "U2") (pin "59") (pinfunction "PB7_59") (pintype "bidirectional"))
    )
    (net (code "20") (name "/LED_GREEN") (class "Default")
      (node (ref "R3") (pin "2") (pinfunction "2_2") (pintype "passive"))
      (node (ref "U2") (pin "58") (pinfunction "PB6_58") (pintype "bidirectional"))
    )
    (net (code "21") (name "/LED_RED") (class "Default")
      (node (ref "R2") (pin "2") (pinfunction "2_2") (pintype "passive"))
      (node (ref "U2") (pin "57") (pinfunction "PB5_57") (pintype "bidirectional"))
    )
    (net (code "22") (name "/MCU_SWCLK") (class "Default")
      (node (ref "R12") (pin "2") (pinfunction "2_2") (pintype "passive"))
      (node (ref "U2") (pin "49") (pinfunction "PA14_49") (pintype "bidirectional"))
    )
    (net (code "23") (name "/MCU_SWDIO") (class "Default")
      (node (ref "R8") (pin "2") (pinfunction "2_2") (pintype "passive"))
      (node (ref "U2") (pin "46") (pinfunction "PA13_46") (pintype "bidirectional"))
    )
    (net (code "24") (name "/MCU_SWO") (class "Default")
      (node (ref "R14") (pin "2") (pinfunction "2_2") (pintype "passive"))
      (node (ref "U2") (pin "55") (pinfunction "PB3_55") (pintype "bidirectional"))
    )
    (net (code "25") (name "/MCU_USB_D_N") (class "Default")
      (node (ref "D2") (pin "6") (pinfunction "IO1_6") (pintype "bidirectional"))
      (node (ref "U2") (pin "44") (pinfunction "PA11_44") (pintype "bidirectional"))
    )
    (net (code "26") (name "/MCU_USB_D_P") (class "Default")
      (node (ref "D2") (pin "4") (pinfunction "IO2_4") (pintype "bidirectional"))
      (node (ref "U2") (pin "45") (pinfunction "PA12_45") (pintype "bidirectional"))
    )
    (net (code "27") (name "/NRST") (class "Default")
      (node (ref "C18") (pin "2") (pinfunction "2_2") (pintype "passive"))
      (node (ref "R15") (pin "2") (pinfunction "2_2") (pintype "passive"))
      (node (ref "SW2") (pin "1") (pinfunction "1_1") (pintype "passive"))
      (node (ref "TP5") (pin "1") (pinfunction "TP_1") (pintype "passive"))
      (node (ref "U2") (pin "7") (pinfunction "NRST_7") (pintype "bidirectional"))
    )
    (net (code "28") (name "/SWD_NRST") (class "Default")
      (node (ref "J3") (pin "5") (pinfunction "5_5") (pintype "passive"))
      (node (ref "R15") (pin "1") (pinfunction "1_1") (pintype "passive"))
    )
    (net (code "29") (name "/SWD_SWCLK") (class "Default")
      (node (ref "J3") (pin "3") (pinfunction "3_3") (pintype "passive"))
      (node (ref "R12") (pin "1") (pinfunction "1_1") (pintype "passive"))
    )
    (net (code "30") (name "/SWD_SWDIO") (class "Default")
      (node (ref "J3") (pin "2") (pinfunction "2_2") (pintype "passive"))
      (node (ref "R8") (pin "1") (pinfunction "1_1") (pintype "passive"))
    )
    (net (code "31") (name "/SWD_SWO") (class "Default")
      (node (ref "J3") (pin "4") (pinfunction "4_4") (pintype "passive"))
      (node (ref "R14") (pin "1") (pinfunction "1_1") (pintype "passive"))
    )
    (net (code "32") (name "/TFT_CS") (class "Default")
      (node (ref "J2") (pin "3") (pinfunction "3_3") (pintype "passive"))
      (node (ref "U2") (pin "33") (pinfunction "PB12_33") (pintype "bidirectional"))
    )
    (net (code "33") (name "/TFT_DC") (class "Default")
      (node (ref "J2") (pin "5") (pinfunction "5_5") (pintype "passive"))
      (node (ref "U2") (pin "37") (pinfunction "PC6_37") (pintype "bidirectional"))
    )
    (net (code "34") (name "/TFT_MOSI") (class "Default")
      (node (ref "R17") (pin "1") (pinfunction "1_1") (pintype "passive"))
      (node (ref "U2") (pin "36") (pinfunction "PB15_36") (pintype "bidirectional"))
    )
    (net (code "35") (name "/TFT_RST") (class "Default")
      (node (ref "J2") (pin "4") (pinfunction "4_4") (pintype "passive"))
      (node (ref "U2") (pin "38") (pinfunction "PC7_38") (pintype "bidirectional"))
    )
    (net (code "36") (name "/TFT_SCK") (class "Default")
      (node (ref "R18") (pin "1") (pinfunction "1_1") (pintype "passive"))
      (node (ref "U2") (pin "34") (pinfunction "PB13_34") (pintype "bidirectional"))
    )
    (net (code "37") (name "/USB_CC1") (class "Default")
      (node (ref "J1") (pin "A5") (pinfunction "CC1_A5") (pintype "passive"))
      (node (ref "R7") (pin "2") (pinfunction "2_2") (pintype "passive"))
    )
    (net (code "38") (name "/USB_CC2") (class "Default")
      (node (ref "J1") (pin "B5") (pinfunction "CC2_B5") (pintype "passive"))
      (node (ref "R6") (pin "2") (pinfunction "2_2") (pintype "passive"))
    )
    (net (code "39") (name "/USB_D_N") (class "Default")
      (node (ref "D2") (pin "1") (pinfunction "IO1_1") (pintype "bidirectional"))
      (node (ref "J1") (pin "A7") (pinfunction "Dn1_A7") (pintype "passive"))
      (node (ref "J1") (pin "B7") (pinfunction "Dn2_B7") (pintype "passive"))
    )
    (net (code "40") (name "/USB_D_P") (class "Default")
      (node (ref "D2") (pin "3") (pinfunction "IO2_3") (pintype "bidirectional"))
      (node (ref "J1") (pin "A6") (pinfunction "Dp1_A6") (pintype "passive"))
      (node (ref "J1") (pin "B6") (pinfunction "Dp2_B6") (pintype "passive"))
    )
    (net (code "41") (name "/VCAP") (class "Default")
      (node (ref "C13") (pin "2") (pinfunction "2_2") (pintype "passive"))
      (node (ref "U2") (pin "30") (pinfunction "VCAP_30") (pintype "power_in"))
    )
    (net (code "42") (name "/VCO_TUN") (class "Default")
      (node (ref "C30") (pin "1") (pinfunction "1_1") (pintype "passive"))
      (node (ref "J4") (pin "11") (pinfunction "11_11") (pintype "passive"))
    )
    (net (code "43") (name "/Vcom1") (class "Default")
      (node (ref "C19") (pin "2") (pinfunction "2_2") (pintype "passive"))
      (node (ref "R10") (pin "1") (pinfunction "1_1") (pintype "passive"))
      (node (ref "R11") (pin "2") (pinfunction "2_2") (pintype "passive"))
      (node (ref "R16") (pin "2") (pinfunction "2_2") (pintype "passive"))
      (node (ref "R9") (pin "2") (pinfunction "2_2") (pintype "passive"))
    )
    (net (code "44") (name "/Vcom2") (class "Default")
      (node (ref "C25") (pin "2") (pinfunction "2_2") (pintype "passive"))
      (node (ref "R20") (pin "2") (pinfunction "2_2") (pintype "passive"))
      (node (ref "R21") (pin "1") (pinfunction "1_1") (pintype "passive"))
      (node (ref "R22") (pin "2") (pinfunction "2_2") (pintype "passive"))
      (node (ref "R27") (pin "2") (pinfunction "2_2") (pintype "passive"))
    )
    (net (code "45") (name "GND") (class "Default")
      (node (ref "C1") (pin "1") (pinfunction "1_1") (pintype "passive"))
      (node (ref "C10") (pin "1") (pinfunction "1_1") (pintype "passive"))
      (node (ref "C11") (pin "1") (pinfunction "1_1") (pintype "passive"))
      (node (ref "C12") (pin "1") (pinfunction "1_1") (pintype "passive"))
      (node (ref "C13") (pin "1") (pinfunction "1_1") (pintype "passive"))
      (node (ref "C14") (pin "1") (pinfunction "1_1") (pintype "passive"))
      (node (ref "C15") (pin "1") (pinfunction "1_1") (pintype "passive"))
      (node (ref "C16") (pin "1") (pinfunction "1_1") (pintype "passive"))
      (node (ref "C17") (pin "1") (pinfunction "1_1") (pintype "passive"))
      (node (ref "C18") (pin "1") (pinfunction "1_1") (pintype "passive"))
      (node (ref "C2") (pin "1") (pinfunction "1_1") (pintype "passive"))
      (node (ref "C20") (pin "1") (pinfunction "1_1") (pintype "passive"))
      (node (ref "C22") (pin "1") (pinfunction "1_1") (pintype "passive"))
      (node (ref "C23") (pin "2") (pinfunction "2_2") (pintype "passive"))
      (node (ref "C25") (pin "1") (pinfunction "1_1") (pintype "passive"))
      (node (ref "C26") (pin "1") (pinfunction "1_1") (pintype "passive"))
      (node (ref "C28") (pin "1") (pinfunction "1_1") (pintype "passive"))
      (node (ref "C29") (pin "1") (pinfunction "1_1") (pintype "passive"))
      (node (ref "C3") (pin "1") (pinfunction "1_1") (pintype "passive"))
      (node (ref "C31") (pin "1") (pinfunction "1_1") (pintype "passive"))
      (node (ref "C32") (pin "2") (pinfunction "2_2") (pintype "passive"))
      (node (ref "C4") (pin "1") (pinfunction "1_1") (pintype "passive"))
      (node (ref "C5") (pin "1") (pinfunction "1_1") (pintype "passive"))
      (node (ref "C6") (pin "1") (pinfunction "1_1") (pintype "passive"))
      (node (ref "C7") (pin "1") (pinfunction "1_1") (pintype "passive"))
      (node (ref "C8") (pin "1") (pinfunction "1_1") (pintype "passive"))
      (node (ref "C9") (pin "1") (pinfunction "1_1") (pintype "passive"))
      (node (ref "D1") (pin "K") (pinfunction "K_K") (pintype "passive"))
      (node (ref "D2") (pin "2") (pinfunction "GND_2") (pintype "power_in"))
      (node (ref "J1") (pin "A1B12") (pinfunction "GND_A1B12") (pintype "passive"))
      (node (ref "J1") (pin "B1A12") (pinfunction "GND_B1A12") (pintype "passive"))
      (node (ref "J1") (pin "SH") (pinfunction "SHIELD_SH") (pintype "passive"))
      (node (ref "J2") (pin "2") (pinfunction "2_2") (pintype "passive"))
      (node (ref "J3") (pin "6") (pinfunction "6_6") (pintype "passive"))
      (node (ref "J4") (pin "10") (pinfunction "10_10") (pintype "passive"))
      (node (ref "J4") (pin "12") (pinfunction "12_12") (pintype "passive"))
      (node (ref "J4") (pin "15") (pinfunction "15_15") (pintype "passive"))
      (node (ref "J4") (pin "4") (pinfunction "4_4") (pintype "passive"))
      (node (ref "J4") (pin "7") (pinfunction "7_7") (pintype "passive"))
      (node (ref "R11") (pin "1") (pinfunction "1_1") (pintype "passive"))
      (node (ref "R22") (pin "1") (pinfunction "1_1") (pintype "passive"))
      (node (ref "R5") (pin "1") (pinfunction "1_1") (pintype "passive"))
      (node (ref "R6") (pin "1") (pinfunction "1_1") (pintype "passive"))
      (node (ref "R7") (pin "1") (pinfunction "1_1") (pintype "passive"))
      (node (ref "SW2") (pin "2") (pinfunction "2_2") (pintype "passive"))
      (node (ref "U1") (pin "2") (pinfunction "GND_2") (pintype "power_in"))
      (node (ref "U2") (pin "12") (pinfunction "VSSA_12") (pintype "power_in"))
      (node (ref "U2") (pin "18") (pinfunction "VSS_18") (pintype "power_in"))
      (node (ref "U2") (pin "31") (pinfunction "VSS_31") (pintype "power_in"))
      (node (ref "U2") (pin "47") (pinfunction "VSS_47") (pintype "power_in"))
      (node (ref "U2") (pin "63") (pinfunction "VSS_63") (pintype "power_in"))
      (node (ref "U3") (pin "4") (pinfunction "V-_4") (pintype "power_in"))
      (node (ref "U4") (pin "4") (pinfunction "V-_4") (pintype "power_in"))
      (node (ref "U5") (pin "4") (pinfunction "V-_4") (pintype "power_in"))
      (node (ref "X1") (pin "2") (pinfunction "2_2") (pintype "passive"))
      (node (ref "X1") (pin "4") (pinfunction "4_4") (pintype "passive"))
    )
    (net (code "46") (name "Net-(D1-PadA)") (class "Default")
      (node (ref "D1") (pin "A") (pinfunction "A_A") (pintype "passive"))
      (node (ref "R1") (pin "2") (pinfunction "2_2") (pintype "passive"))
    )
    (net (code "47") (name "Net-(D3-CB)") (class "Default")
      (node (ref "D3") (pin "3") (pinfunction "CB_3") (pintype "passive"))
      (node (ref "R4") (pin "1") (pinfunction "1_1") (pintype "passive"))
    )
    (net (code "48") (name "Net-(D3-CG)") (class "Default")
      (node (ref "D3") (pin "2") (pinfunction "CG_2") (pintype "passive"))
      (node (ref "R3") (pin "1") (pinfunction "1_1") (pintype "passive"))
    )
    (net (code "49") (name "Net-(D3-CR)") (class "Default")
      (node (ref "D3") (pin "1") (pinfunction "CR_1") (pintype "passive"))
      (node (ref "R2") (pin "1") (pinfunction "1_1") (pintype "passive"))
    )
    (net (code "50") (name "Net-(J2-Pad6)") (class "Default")
      (node (ref "J2") (pin "6") (pinfunction "6_6") (pintype "passive"))
      (node (ref "R17") (pin "2") (pinfunction "2_2") (pintype "passive"))
    )
    (net (code "51") (name "Net-(J2-Pad7)") (class "Default")
      (node (ref "J2") (pin "7") (pinfunction "7_7") (pintype "passive"))
      (node (ref "R18") (pin "2") (pinfunction "2_2") (pintype "passive"))
    )
    (net (code "52") (name "Net-(U1-BYP)") (class "Default")
      (node (ref "C6") (pin "2") (pinfunction "2_2") (pintype "passive"))
      (node (ref "U1") (pin "4") (pinfunction "BYP_4") (pintype "passive"))
    )
    (net (code "53") (name "Net-(U3A-IN_A+)") (class "Default")
      (node (ref "C21") (pin "1") (pinfunction "1_1") (pintype "passive"))
      (node (ref "R9") (pin "1") (pinfunction "1_1") (pintype "passive"))
      (node (ref "U3") (pin "3") (pinfunction "IN_A+_3") (pintype "input"))
    )
    (net (code "54") (name "Net-(U3A-IN_A-)") (class "Default")
      (node (ref "R13") (pin "1") (pinfunction "1_1") (pintype "passive"))
      (node (ref "U3") (pin "1") (pinfunction "VOUTA_1") (pintype "output"))
      (node (ref "U3") (pin "2") (pinfunction "IN_A-_2") (pintype "input"))
    )
    (net (code "55") (name "Net-(U3B-IN_B+)") (class "Default")
      (node (ref "C24") (pin "1") (pinfunction "1_1") (pintype "passive"))
      (node (ref "R16") (pin "1") (pinfunction "1_1") (pintype "passive"))
      (node (ref "U3") (pin "5") (pinfunction "IN_B+_5") (pintype "tri_state"))
    )
    (net (code "56") (name "Net-(U3B-IN_B-)") (class "Default")
      (node (ref "R19") (pin "1") (pinfunction "1_1") (pintype "passive"))
      (node (ref "U3") (pin "6") (pinfunction "IN_B-_6") (pintype "tri_state"))
      (node (ref "U3") (pin "7") (pinfunction "VOUTB_7") (pintype "output"))
    )
    (net (code "57") (name "Net-(U4A-IN_A+)") (class "Default")
      (node (ref "C27") (pin "1") (pinfunction "1_1") (pintype "passive"))
      (node (ref "R20") (pin "1") (pinfunction "1_1") (pintype "passive"))
      (node (ref "U4") (pin "3") (pinfunction "IN_A+_3") (pintype "input"))
    )
    (net (code "58") (name "Net-(U4A-IN_A-)") (class "Default")
      (node (ref "R23") (pin "1") (pinfunction "1_1") (pintype "passive"))
      (node (ref "U4") (pin "1") (pinfunction "VOUTA_1") (pintype "output"))
      (node (ref "U4") (pin "2") (pinfunction "IN_A-_2") (pintype "input"))
    )
    (net (code "59") (name "Net-(U4B-IN_B+)") (class "Default")
      (node (ref "C33") (pin "1") (pinfunction "1_1") (pintype "passive"))
      (node (ref "R27") (pin "1") (pinfunction "1_1") (pintype "passive"))
      (node (ref "U4") (pin "5") (pinfunction "IN_B+_5") (pintype "tri_state"))
    )
    (net (code "60") (name "Net-(U4B-IN_B-)") (class "Default")
      (node (ref "R28") (pin "1") (pinfunction "1_1") (pintype "passive"))
      (node (ref "U4") (pin "6") (pinfunction "IN_B-_6") (pintype "tri_state"))
      (node (ref "U4") (pin "7") (pinfunction "VOUTB_7") (pintype "output"))
    )
    (net (code "61") (name "Net-(U5A-IN1-)") (class "Default")
      (node (ref "R26") (pin "1") (pinfunction "1_1") (pintype "passive"))
      (node (ref "U5") (pin "1") (pinfunction "OUT1_1") (pintype "output"))
      (node (ref "U5") (pin "2") (pinfunction "IN1-_2") (pintype "tri_state"))
    )
    (net (code "62") (name "Net-(U5B-IN2+)") (class "Default")
      (node (ref "C31") (pin "2") (pinfunction "2_2") (pintype "passive"))
      (node (ref "R26") (pin "2") (pinfunction "2_2") (pintype "passive"))
      (node (ref "U5") (pin "5") (pinfunction "IN2+_5") (pintype "input"))
    )
    (net (code "63") (name "Net-(U5B-IN2-)") (class "Default")
      (node (ref "C30") (pin "2") (pinfunction "2_2") (pintype "passive"))
      (node (ref "U5") (pin "6") (pinfunction "IN2-_6") (pintype "input"))
      (node (ref "U5") (pin "7") (pinfunction "OUT2_7") (pintype "output"))
    )
    (net (code "64") (name "unconnected-(C19-Pad1)") (class "Default")
      (node (ref "C19") (pin "1") (pinfunction "1_1") (pintype "passive"))
    )
    (net (code "65") (name "unconnected-(J1-SBU1-PadA8)") (class "Default")
      (node (ref "J1") (pin "A8") (pinfunction "SBU1_A8") (pintype "passive+no_connect"))
    )
    (net (code "66") (name "unconnected-(J1-SBU2-PadB8)") (class "Default")
      (node (ref "J1") (pin "B8") (pinfunction "SBU2_B8") (pintype "passive+no_connect"))
    )
    (net (code "67") (name "unconnected-(J2-Pad9)") (class "Default")
      (node (ref "J2") (pin "9") (pinfunction "9_9") (pintype "passive+no_connect"))
    )
    (net (code "68") (name "unconnected-(J2-Pad10)") (class "Default")
      (node (ref "J2") (pin "10") (pinfunction "10_10") (pintype "passive+no_connect"))
    )
    (net (code "69") (name "unconnected-(J2-Pad11)") (class "Default")
      (node (ref "J2") (pin "11") (pinfunction "11_11") (pintype "passive+no_connect"))
    )
    (net (code "70") (name "unconnected-(J2-Pad12)") (class "Default")
      (node (ref "J2") (pin "12") (pinfunction "12_12") (pintype "passive+no_connect"))
    )
    (net (code "71") (name "unconnected-(J2-Pad13)") (class "Default")
      (node (ref "J2") (pin "13") (pinfunction "13_13") (pintype "passive+no_connect"))
    )
    (net (code "72") (name "unconnected-(J2-Pad14)") (class "Default")
      (node (ref "J2") (pin "14") (pinfunction "14_14") (pintype "passive+no_connect"))
    )
    (net (code "73") (name "unconnected-(U2A-PA0-Pad14)") (class "Default")
      (node (ref "U2") (pin "14") (pinfunction "PA0_14") (pintype "bidirectional+no_connect"))
    )
    (net (code "74") (name "unconnected-(U2A-PA3-Pad17)") (class "Default")
      (node (ref "U2") (pin "17") (pinfunction "PA3_17") (pintype "bidirectional+no_connect"))
    )
    (net (code "75") (name "unconnected-(U2A-PA4-Pad20)") (class "Default")
      (node (ref "U2") (pin "20") (pinfunction "PA4_20") (pintype "bidirectional+no_connect"))
    )
    (net (code "76") (name "unconnected-(U2A-PA6-Pad22)") (class "Default")
      (node (ref "U2") (pin "22") (pinfunction "PA6_22") (pintype "bidirectional+no_connect"))
    )
    (net (code "77") (name "unconnected-(U2A-PA8-Pad41)") (class "Default")
      (node (ref "U2") (pin "41") (pinfunction "PA8_41") (pintype "bidirectional+no_connect"))
    )
    (net (code "78") (name "unconnected-(U2A-PA9-Pad42)") (class "Default")
      (node (ref "U2") (pin "42") (pinfunction "PA9_42") (pintype "bidirectional+no_connect"))
    )
    (net (code "79") (name "unconnected-(U2A-PA10-Pad43)") (class "Default")
      (node (ref "U2") (pin "43") (pinfunction "PA10_43") (pintype "bidirectional+no_connect"))
    )
    (net (code "80") (name "unconnected-(U2A-PA15-Pad50)") (class "Default")
      (node (ref "U2") (pin "50") (pinfunction "PA15_50") (pintype "bidirectional+no_connect"))
    )
    (net (code "81") (name "unconnected-(U2A-PB0-Pad26)") (class "Default")
      (node (ref "U2") (pin "26") (pinfunction "PB0_26") (pintype "bidirectional+no_connect"))
    )
    (net (code "82") (name "unconnected-(U2A-PB1-Pad27)") (class "Default")
      (node (ref "U2") (pin "27") (pinfunction "PB1_27") (pintype "bidirectional+no_connect"))
    )
    (net (code "83") (name "unconnected-(U2A-PB2-Pad28)") (class "Default")
      (node (ref "U2") (pin "28") (pinfunction "PB2_28") (pintype "bidirectional+no_connect"))
    )
    (net (code "84") (name "unconnected-(U2A-PB8-Pad61)") (class "Default")
      (node (ref "U2") (pin "61") (pinfunction "PB8_61") (pintype "bidirectional+no_connect"))
    )
    (net (code "85") (name "unconnected-(U2A-PB9-Pad62)") (class "Default")
      (node (ref "U2") (pin "62") (pinfunction "PB9_62") (pintype "power_in+no_connect"))
    )
    (net (code "86") (name "unconnected-(U2A-PB10-Pad29)") (class "Default")
      (node (ref "U2") (pin "29") (pinfunction "PB10_29") (pintype "bidirectional+no_connect"))
    )
    (net (code "87") (name "unconnected-(U2A-PB14-Pad35)") (class "Default")
      (node (ref "U2") (pin "35") (pinfunction "PB14_35") (pintype "bidirectional+no_connect"))
    )
    (net (code "88") (name "unconnected-(U2A-PC0-Pad8)") (class "Default")
      (node (ref "U2") (pin "8") (pinfunction "PC0_8") (pintype "bidirectional+no_connect"))
    )
    (net (code "89") (name "unconnected-(U2A-PC3-Pad11)") (class "Default")
      (node (ref "U2") (pin "11") (pinfunction "PC3_11") (pintype "bidirectional+no_connect"))
    )
    (net (code "90") (name "unconnected-(U2A-PC4-Pad24)") (class "Default")
      (node (ref "U2") (pin "24") (pinfunction "PC4_24") (pintype "bidirectional+no_connect"))
    )
    (net (code "91") (name "unconnected-(U2A-PC5-Pad25)") (class "Default")
      (node (ref "U2") (pin "25") (pinfunction "PC5_25") (pintype "bidirectional+no_connect"))
    )
    (net (code "92") (name "unconnected-(U2A-PC8-Pad39)") (class "Default")
      (node (ref "U2") (pin "39") (pinfunction "PC8_39") (pintype "bidirectional+no_connect"))
    )
    (net (code "93") (name "unconnected-(U2A-PC9-Pad40)") (class "Default")
      (node (ref "U2") (pin "40") (pinfunction "PC9_40") (pintype "bidirectional+no_connect"))
    )
    (net (code "94") (name "unconnected-(U2A-PC10-Pad51)") (class "Default")
      (node (ref "U2") (pin "51") (pinfunction "PC10_51") (pintype "bidirectional+no_connect"))
    )
    (net (code "95") (name "unconnected-(U2A-PC11-Pad52)") (class "Default")
      (node (ref "U2") (pin "52") (pinfunction "PC11_52") (pintype "bidirectional+no_connect"))
    )
    (net (code "96") (name "unconnected-(U2A-PC12-Pad53)") (class "Default")
      (node (ref "U2") (pin "53") (pinfunction "PC12_53") (pintype "bidirectional+no_connect"))
    )
    (net (code "97") (name "unconnected-(U2A-PC13-Pad2)") (class "Default")
      (node (ref "U2") (pin "2") (pinfunction "PC13_2") (pintype "bidirectional+no_connect"))
    )
    (net (code "98") (name "unconnected-(U2A-PC14-OSC32_IN-Pad3)") (class "Default")
      (node (ref "U2") (pin "3") (pinfunction "PC14-OSC32_IN_3") (pintype "bidirectional+no_connect"))
    )
    (net (code "99") (name "unconnected-(U2A-PC15-OSC32_OUT-Pad4)") (class "Default")
      (node (ref "U2") (pin "4") (pinfunction "PC15-OSC32_OUT_4") (pintype "bidirectional+no_connect"))
    )
    (net (code "100") (name "unconnected-(U2A-PD2-Pad54)") (class "Default")
      (node (ref "U2") (pin "54") (pinfunction "PD2_54") (pintype "bidirectional+no_connect"))
    )
  )
)
